# 12V_to5v_5V_to_3_3V.net
KiCad netlist of a schematic drawn in Altium Designer
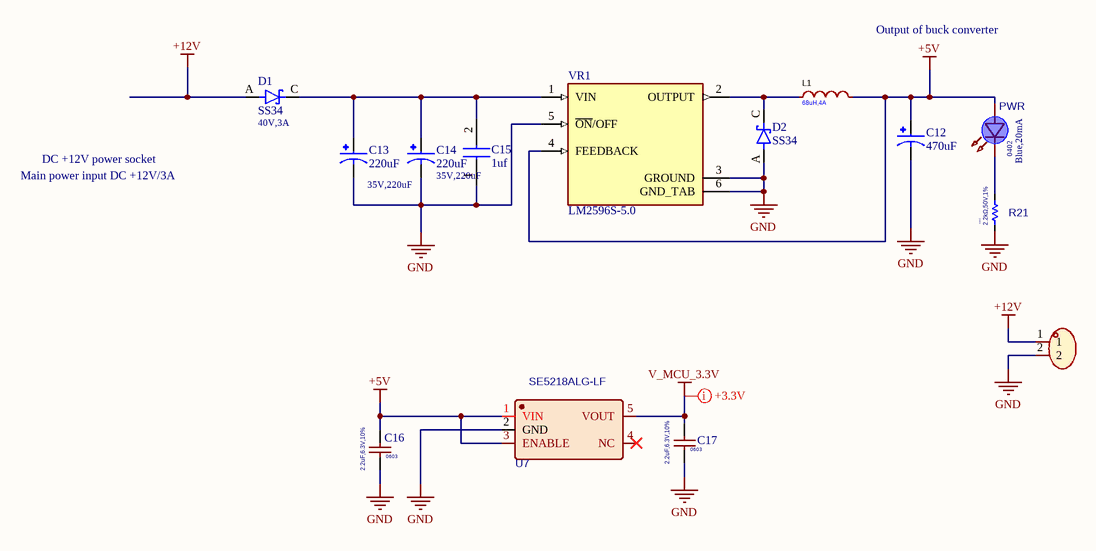
[diagram p0: 12V to5v_5V to 3.3V.SchDoc]

(export (version "E")
  (design (tool "Eeschema 10.0.6"))
  (components
    (comp (ref "C12")
      (value "470uF")
      (footprint "Plugin,6.3x8mm")
      (description "6.3V 470uF ±20% Plugin,6.3x8mm Solid Capacitors ROHS")
      (fields (field (name "MPN") "EEE-HC1H101P") (field (name "MANUFACTURER") "Panasonic"))
      (libsource (lib "RCL") (part "SPTOJM471E08OR"))
    )
    (comp (ref "C13")
      (value "220uF")
      (footprint "Plugin,6.3x8mm")
      (description "220uF 35V ±20% Plugin,D6.3xL11mm Aluminum Electrolytic Capacitors - Leaded ROHS")
      (fields
        (field (name "MPN") "NPXC1101V221MJTM")
        (field (name "MANUFACTURER") "Ymin")
        (field (name "ALTIUM_VALUE") "35V,220uF")
      )
      (libsource (lib "RCL") (part "NPXC1101V221MJTM"))
    )
    (comp (ref "C14")
      (value "220uF")
      (footprint "Plugin,6.3x8mm")
      (description "220uF 35V ±20% Plugin,D6.3xL11mm Aluminum Electrolytic Capacitors - Leaded ROHS")
      (fields
        (field (name "MPN") "NPXC1101V221MJTM")
        (field (name "MANUFACTURER") "Ymin")
        (field (name "ALTIUM_VALUE") "35V,220uF")
      )
      (libsource (lib "RCL") (part "NPXC1101V221MJTM"))
    )
    (comp (ref "C15")
      (value "1uf")
      (footprint "C0805")
      (description "50V 1uF X7R ±10% 0805 Multilayer Ceramic Capacitors MLCC - SMD/SMT ROHS")
      (fields (field (name "MANUFACTURER") "KEMET") (field (name "MPN") "CC0603JRNPO9BN180"))
      (libsource (lib "RCL") (part "CL21B105KBFNNNE"))
    )
    (comp (ref "C16")
      (value "2.2uF,6.3V,10%")
      (footprint "C0603")
      (description "CAP CER 2.2UF 6.3V X7R 0603")
      (fields
        (field (name "MANUFACTURER") "TDK Corporation")
        (field (name "MPN") "CGA3E1X7R0J225K080AC")
        (field (name "PACKAGE") "0603")
      )
      (libsource (lib "RCL") (part "CGA3E1X7R0J225K080AC"))
    )
    (comp (ref "C17")
      (value "2.2uF,6.3V,10%")
      (footprint "C0603")
      (description "CAP CER 2.2UF 6.3V X7R 0603")
      (fields
        (field (name "MANUFACTURER") "TDK Corporation")
        (field (name "MPN") "CGA3E1X7R0J225K080AC")
        (field (name "PACKAGE") "0603")
      )
      (libsource (lib "RCL") (part "CGA3E1X7R0J225K080AC"))
    )
    (comp (ref "D1")
      (value "SS34")
      (footprint "SMA")
      (description "Diode Schottky 40V 3A 2-Pin SMC T/R")
      (fields (field (name "ALTIUM_VALUE") "40V,3A"))
      (libsource (lib "RCL") (part "SS34"))
    )
    (comp (ref "D2")
      (value "SS34")
      (footprint "SMA")
      (description "Diode Schottky 40V 3A 2-Pin SMC T/R")
      (libsource (lib "RCL") (part "SS34"))
    )
    (comp (ref "L1")
      (value "68uH,4A")
      (footprint "ind_SMD_12.3x12.3mm")
      (description "2.1A 68uH Shielded inductor ±20% 4A SMD,12.3x12.3mm Power Inductors ROHS")
      (fields (field (name "MANUFACTURER") "SXN(顺翔诺)") (field (name "MPN") "SMDRI127-680MT"))
      (libsource (lib "RCL") (part "SMDRI127-680MT"))
    )
    (comp (ref "PWR")
      (value "Blue,20mA")
      (footprint "LED 0402")
      (fields
        (field (name "MANUFACTURER") "XINGLIGHT")
        (field (name "MPN") "XL-1005UBC")
        (field (name "PACKAGE") "0402")
      )
      (libsource (lib "LED") (part "XL-1005UBC"))
    )
    (comp (ref "R21")
      (value "2.2kΩ,50V,1%")
      (footprint "R0402")
      (description "62.5mW Thick Film Resistors 50V ±100ppm/℃ ±1% 2.2kΩ 0402 Chip Resistor - Surface Mount ROHS")
      (fields
        (field (name "MPN") "RC0402FR-072K2L")
        (field (name "MANUFACTURER") "YAGEO")
        (field (name "PACKAGE") "0402")
      )
      (libsource (lib "RCL") (part "RC0402FR-072K2L"))
    )
    (comp (ref "U5")
      (value "DB128L-5.08-2P-GN-S")
      (footprint "2P_P=5.08mm")
      (description "1x2P 18A -40℃~+105℃ 250V Green 12~30 Direct Insert 5.08mm 2.5 1 2 Plugin,P=5.08mm Screw Terminal")
      (fields (field (name "MANUFACTURER") "DORABO"))
      (libsource (lib "connector_button") (part "DB128L-5.08-2P-GN-S"))
    )
    (comp (ref "U7")
      (value "SE5218ALG-LF")
      (footprint "SOT-23-5")
      (fields (field (name "MANUFACTURER") "SEAWARD(思旺)"))
      (libsource (lib "IC") (part "SE5218ALG-LF"))
    )
    (comp (ref "VR1")
      (value "LM2596S-5.0")
      (footprint "TO-263-5")
      (description "Step-down type Fixed 40V~40V 5V 3A TO-263-5 DC-DC Converters ROHS")
      (libsource (lib "IC") (part "LM2596S-5.0"))
    )
  )
  (nets
    (net (code "1") (name "+5V") (class "Default")
      (node (ref "C12") (pin "1") (pinfunction "1_1") (pintype "passive"))
      (node (ref "C16") (pin "1") (pinfunction "1_1") (pintype "passive"))
      (node (ref "L1") (pin "2") (pinfunction "2_2") (pintype "passive"))
      (node (ref "PWR") (pin "2") (pinfunction "A_2") (pintype "passive"))
      (node (ref "U7") (pin "1") (pinfunction "VIN_1") (pintype "passive"))
      (node (ref "U7") (pin "3") (pinfunction "ENABLE_3") (pintype "passive"))
      (node (ref "VR1") (pin "4") (pinfunction "FEEDBACK_4") (pintype "input"))
    )
    (net (code "2") (name "+12V") (class "Default")
      (node (ref "D1") (pin "A") (pinfunction "A_A") (pintype "passive"))
      (node (ref "U5") (pin "1") (pinfunction "1_1") (pintype "passive"))
    )
    (net (code "3") (name "GND") (class "Default")
      (node (ref "C12") (pin "2") (pinfunction "2_2") (pintype "passive"))
      (node (ref "C13") (pin "2") (pinfunction "2_2") (pintype "passive"))
      (node (ref "C14") (pin "2") (pinfunction "2_2") (pintype "passive"))
      (node (ref "C15") (pin "1") (pinfunction "C1_1") (pintype "passive"))
      (node (ref "C16") (pin "2") (pinfunction "2_2") (pintype "passive"))
      (node (ref "C17") (pin "2") (pinfunction "2_2") (pintype "passive"))
      (node (ref "D2") (pin "A") (pinfunction "A_A") (pintype "passive"))
      (node (ref "R21") (pin "1") (pinfunction "1_1") (pintype "passive"))
      (node (ref "U5") (pin "2") (pinfunction "2_2") (pintype "passive"))
      (node (ref "U7") (pin "2") (pinfunction "GND_2") (pintype "passive"))
      (node (ref "VR1") (pin "3") (pinfunction "GROUND_3") (pintype "power_in"))
      (node (ref "VR1") (pin "5") (pinfunction "~{ON}/OFF_5") (pintype "input"))
      (node (ref "VR1") (pin "6") (pinfunction "GND_TAB_6") (pintype "power_in"))
    )
    (net (code "4") (name "Net-(C15-C2)") (class "Default")
      (node (ref "C13") (pin "1") (pinfunction "1_1") (pintype "passive"))
      (node (ref "C14") (pin "1") (pinfunction "1_1") (pintype "passive"))
      (node (ref "C15") (pin "2") (pinfunction "C2_2") (pintype "passive"))
      (node (ref "D1") (pin "C") (pinfunction "K_C") (pintype "passive"))
      (node (ref "VR1") (pin "1") (pinfunction "VIN_1") (pintype "input"))
    )
    (net (code "5") (name "Net-(D2-K)") (class "Default")
      (node (ref "D2") (pin "C") (pinfunction "K_C") (pintype "passive"))
      (node (ref "L1") (pin "1") (pinfunction "1_1") (pintype "passive"))
      (node (ref "VR1") (pin "2") (pinfunction "OUTPUT_2") (pintype "output"))
    )
    (net (code "6") (name "Net-(PWR-K)") (class "Default")
      (node (ref "PWR") (pin "1") (pinfunction "K_1") (pintype "passive"))
      (node (ref "R21") (pin "2") (pinfunction "2_2") (pintype "passive"))
    )
    (net (code "7") (name "V_MCU_3.3V") (class "Default")
      (node (ref "C17") (pin "1") (pinfunction "1_1") (pintype "passive"))
      (node (ref "U7") (pin "5") (pinfunction "VOUT_5") (pintype "passive"))
    )
    (net (code "8") (name "unconnected-(U7-NC-Pad4)") (class "Default")
      (node (ref "U7") (pin "4") (pinfunction "NC_4") (pintype "passive+no_connect"))
    )
  )
)
